# 0007-Optical_Tracker.net
KiCad netlist of a schematic drawn in Altium Designer
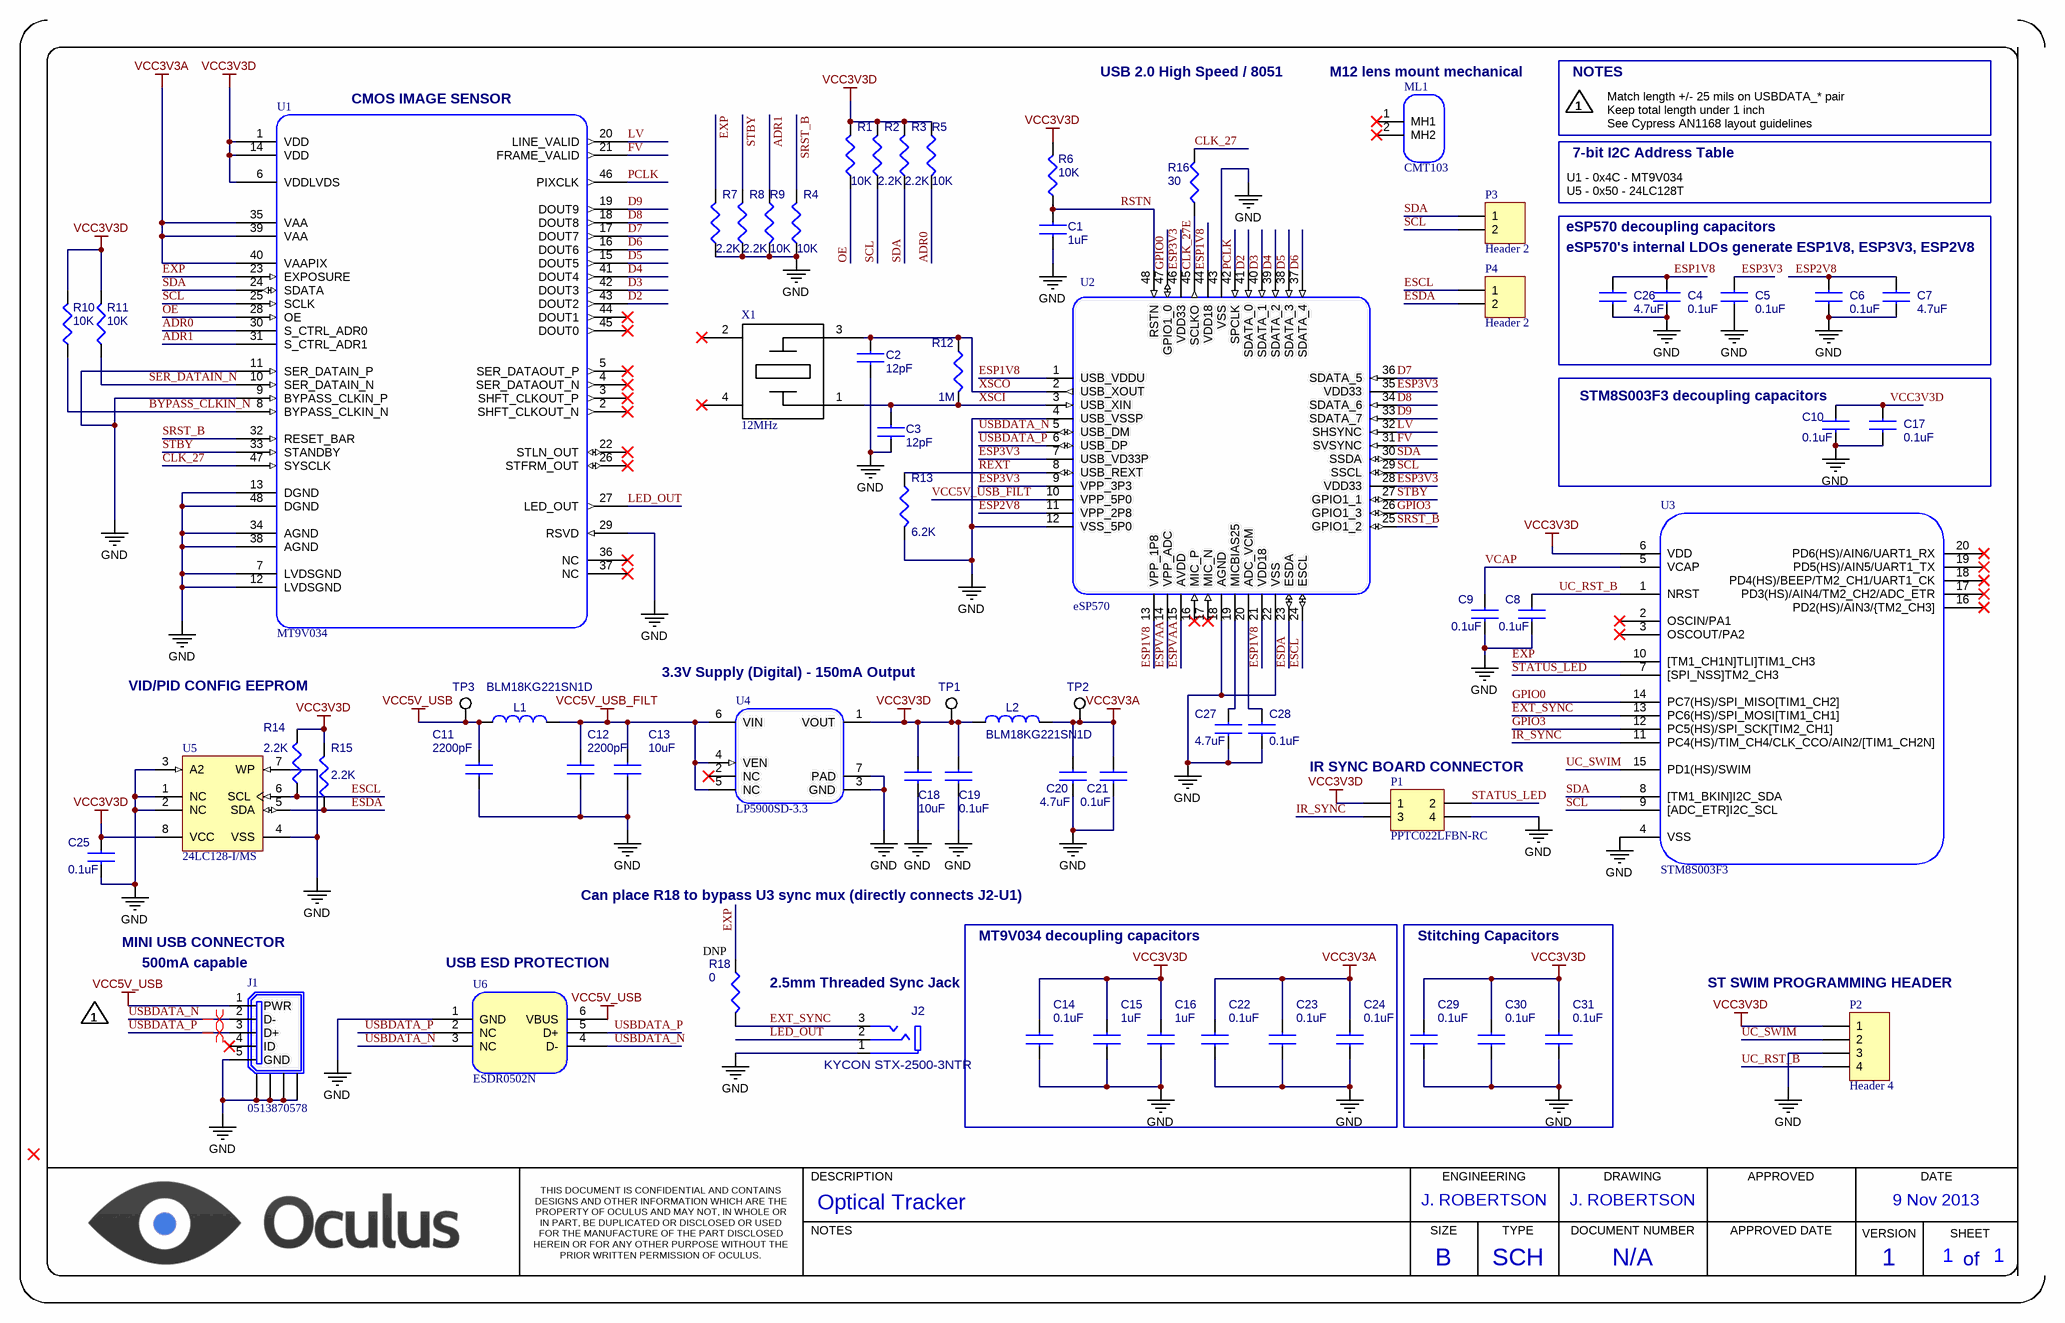
[diagram p0: 0007-Optical_Tracker.SchDoc]

(export (version "E")
  (design (tool "Eeschema 10.0.6"))
  (components
    (comp (ref "C1")
      (value "1uF")
      (footprint "CAP_CERAMIC_0402")
      (description "CAP CER 1UF 6.3V 20% X5R 0402")
      (libsource (lib "SchematicComponents") (part "CAP, CERAMIC"))
    )
    (comp (ref "C2")
      (value "12pF")
      (footprint "CAP_CERAMIC_0402")
      (description "CAP CER 12PF 50V 5% NP0 0402")
      (libsource (lib "SchematicComponents") (part "CAP, CERAMIC"))
    )
    (comp (ref "C3")
      (value "12pF")
      (footprint "CAP_CERAMIC_0402")
      (description "CAP CER 12PF 50V 5% NP0 0402")
      (libsource (lib "SchematicComponents") (part "CAP, CERAMIC"))
    )
    (comp (ref "C4")
      (value "0.1uF")
      (footprint "CAP_CERAMIC_0402")
      (description "CAP CER 0.1UF 6.3V 20% X5R 0402")
      (libsource (lib "SchematicComponents") (part "CAP, CERAMIC"))
    )
    (comp (ref "C5")
      (value "0.1uF")
      (footprint "CAP_CERAMIC_0402")
      (description "CAP CER 0.1UF 6.3V 20% X5R 0402")
      (libsource (lib "SchematicComponents") (part "CAP, CERAMIC"))
    )
    (comp (ref "C6")
      (value "0.1uF")
      (footprint "CAP_CERAMIC_0402")
      (description "CAP CER 0.1UF 6.3V 20% X5R 0402")
      (libsource (lib "SchematicComponents") (part "CAP, CERAMIC"))
    )
    (comp (ref "C7")
      (value "4.7uF")
      (footprint "CAP_CERAMIC_0402")
      (description "CAP CER 4.7UF 6.3V 20% X5R 0402")
      (libsource (lib "SchematicComponents") (part "CAP, CERAMIC"))
    )
    (comp (ref "C8")
      (value "0.1uF")
      (footprint "CAP_CERAMIC_0402")
      (description "CAP CER 0.1UF 6.3V 20% X5R 0402")
      (libsource (lib "SchematicComponents") (part "CAP, CERAMIC"))
    )
    (comp (ref "C9")
      (value "0.1uF")
      (footprint "CAP_CERAMIC_0402")
      (description "CAP CER 0.1UF 6.3V 20% X5R 0402")
      (libsource (lib "SchematicComponents") (part "CAP, CERAMIC"))
    )
    (comp (ref "C10")
      (value "0.1uF")
      (footprint "CAP_CERAMIC_0402")
      (description "CAP CER 0.1UF 6.3V 20% X5R 0402")
      (libsource (lib "SchematicComponents") (part "CAP, CERAMIC"))
    )
    (comp (ref "C11")
      (value "2200pF")
      (footprint "CAP_CERAMIC_0402")
      (description "CAP CER 2200PF 50V 10% X7R 0402")
      (libsource (lib "SchematicComponents") (part "CAP, CERAMIC"))
    )
    (comp (ref "C12")
      (value "2200pF")
      (footprint "CAP_CERAMIC_0402")
      (description "CAP CER 2200PF 50V 10% X7R 0402")
      (libsource (lib "SchematicComponents") (part "CAP, CERAMIC"))
    )
    (comp (ref "C13")
      (value "10uF")
      (footprint "CAP_CERAMIC_0603")
      (description "CAP CER 10UF 6.3V 20% X5R 0603")
      (libsource (lib "SchematicComponents") (part "CAP, CERAMIC"))
    )
    (comp (ref "C14")
      (value "0.1uF")
      (footprint "CAP_CERAMIC_0402")
      (description "CAP CER 0.1UF 6.3V 20% X5R 0402")
      (libsource (lib "SchematicComponents") (part "CAP, CERAMIC"))
    )
    (comp (ref "C15")
      (value "1uF")
      (footprint "CAP_CERAMIC_0402")
      (description "CAP CER 1UF 6.3V 20% X5R 0402")
      (libsource (lib "SchematicComponents") (part "CAP, CERAMIC"))
    )
    (comp (ref "C16")
      (value "1uF")
      (footprint "CAP_CERAMIC_0402")
      (description "CAP CER 1UF 6.3V 20% X5R 0402")
      (libsource (lib "SchematicComponents") (part "CAP, CERAMIC"))
    )
    (comp (ref "C17")
      (value "0.1uF")
      (footprint "CAP_CERAMIC_0402")
      (description "CAP CER 0.1UF 6.3V 20% X5R 0402")
      (libsource (lib "SchematicComponents") (part "CAP, CERAMIC"))
    )
    (comp (ref "C18")
      (value "10uF")
      (footprint "CAP_CERAMIC_0603")
      (description "CAP CER 10UF 6.3V 20% X5R 0603")
      (libsource (lib "SchematicComponents") (part "CAP, CERAMIC"))
    )
    (comp (ref "C19")
      (value "0.1uF")
      (footprint "CAP_CERAMIC_0402")
      (description "CAP CER 0.1UF 6.3V 20% X5R 0402")
      (libsource (lib "SchematicComponents") (part "CAP, CERAMIC"))
    )
    (comp (ref "C20")
      (value "4.7uF")
      (footprint "CAP_CERAMIC_0402")
      (description "CAP CER 4.7UF 6.3V 20% X5R 0402")
      (libsource (lib "SchematicComponents") (part "CAP, CERAMIC"))
    )
    (comp (ref "C21")
      (value "0.1uF")
      (footprint "CAP_CERAMIC_0402")
      (description "CAP CER 0.1UF 6.3V 20% X5R 0402")
      (libsource (lib "SchematicComponents") (part "CAP, CERAMIC"))
    )
    (comp (ref "C22")
      (value "0.1uF")
      (footprint "CAP_CERAMIC_0402")
      (description "CAP CER 0.1UF 6.3V 20% X5R 0402")
      (libsource (lib "SchematicComponents") (part "CAP, CERAMIC"))
    )
    (comp (ref "C23")
      (value "0.1uF")
      (footprint "CAP_CERAMIC_0402")
      (description "CAP CER 0.1UF 6.3V 20% X5R 0402")
      (libsource (lib "SchematicComponents") (part "CAP, CERAMIC"))
    )
    (comp (ref "C24")
      (value "0.1uF")
      (footprint "CAP_CERAMIC_0402")
      (description "CAP CER 0.1UF 6.3V 20% X5R 0402")
      (libsource (lib "SchematicComponents") (part "CAP, CERAMIC"))
    )
    (comp (ref "C25")
      (value "0.1uF")
      (footprint "CAP_CERAMIC_0402")
      (description "CAP CER 0.1UF 6.3V 20% X5R 0402")
      (libsource (lib "SchematicComponents") (part "CAP, CERAMIC"))
    )
    (comp (ref "C26")
      (value "4.7uF")
      (footprint "CAP_CERAMIC_0402")
      (description "CAP CER 4.7UF 6.3V 20% X5R 0402")
      (libsource (lib "SchematicComponents") (part "CAP, CERAMIC"))
    )
    (comp (ref "C27")
      (value "4.7uF")
      (footprint "CAP_CERAMIC_0402")
      (description "CAP CER 4.7UF 6.3V 20% X5R 0402")
      (libsource (lib "SchematicComponents") (part "CAP, CERAMIC"))
    )
    (comp (ref "C28")
      (value "0.1uF")
      (footprint "CAP_CERAMIC_0402")
      (description "CAP CER 0.1UF 6.3V 20% X5R 0402")
      (libsource (lib "SchematicComponents") (part "CAP, CERAMIC"))
    )
    (comp (ref "C29")
      (value "0.1uF")
      (footprint "CAP_CERAMIC_0402")
      (description "CAP CER 0.1UF 6.3V 20% X5R 0402")
      (libsource (lib "SchematicComponents") (part "CAP, CERAMIC"))
    )
    (comp (ref "C30")
      (value "0.1uF")
      (footprint "CAP_CERAMIC_0402")
      (description "CAP CER 0.1UF 6.3V 20% X5R 0402")
      (libsource (lib "SchematicComponents") (part "CAP, CERAMIC"))
    )
    (comp (ref "C31")
      (value "0.1uF")
      (footprint "CAP_CERAMIC_0402")
      (description "CAP CER 0.1UF 6.3V 20% X5R 0402")
      (libsource (lib "SchematicComponents") (part "CAP, CERAMIC"))
    )
    (comp (ref "J1")
      (value "0513870578")
      (footprint "0513870578")
      (description "CONN RECEPT MINIUSB R/A 5POS SMD")
      (libsource (lib "SchematicComponents") (part "0513870578"))
    )
    (comp (ref "J2")
      (value "KYCON STX-2500-3NTR")
      (footprint "KYCON_STX2500")
      (description "Phone Connectors SJ 2.5MM SMT 3POS")
      (libsource (lib "*") (part "AUDIO_JACK_3P"))
    )
    (comp (ref "L1")
      (value "BLM18KG221SN1D")
      (footprint "INDUCTOR_0603")
      (description "FERRITE CHIP 220 OHM 2200MA 0603")
      (fields (field (name "MANUFACTURER") "Murata"))
      (libsource (lib "SchematicComponents") (part "INDUCTOR"))
    )
    (comp (ref "L2")
      (value "BLM18KG221SN1D")
      (footprint "INDUCTOR_0603")
      (description "FERRITE CHIP 220 OHM 2200MA 0603")
      (fields (field (name "MANUFACTURER") "Murata"))
      (libsource (lib "SchematicComponents") (part "INDUCTOR"))
    )
    (comp (ref "ML1")
      (value "CMT103")
      (footprint "CMT103")
      (description "Lens holder, M12x0.5, 16.2, centered")
      (libsource (lib "SchematicComponents") (part "CMT103"))
    )
    (comp (ref "P1")
      (value "PPTC022LFBN-RC")
      (footprint "HDR2X2")
      (description "Header, 2-Pin, Dual row")
      (libsource (lib "Miscellaneous Connectors") (part "Header 2X2"))
    )
    (comp (ref "P2")
      (value "Header 4")
      (footprint "HDR1X4")
      (description "Header, 4-Pin")
      (libsource (lib "Miscellaneous Connectors") (part "Header 4"))
    )
    (comp (ref "P3")
      (value "Header 2")
      (footprint "HDR1X2")
      (description "Header, 2-Pin")
      (fields (field (name "PUBLISHER") "Altium Limited"))
      (libsource (lib "Miscellaneous Connectors") (part "Header 2"))
    )
    (comp (ref "P4")
      (value "Header 2")
      (footprint "HDR1X2")
      (description "Header, 2-Pin")
      (fields (field (name "PUBLISHER") "Altium Limited"))
      (libsource (lib "Miscellaneous Connectors") (part "Header 2"))
    )
    (comp (ref "R1")
      (value "10K")
      (footprint "RESISTOR_0402")
      (description "RES 10K OHM 1/10W 1% 0402 SMD")
      (libsource (lib "SchematicComponents") (part "RESISTOR"))
    )
    (comp (ref "R2")
      (value "2.2K")
      (footprint "RESISTOR_0402")
      (description "RES 2.2K OHM 1/10W 1% 0402 SMD")
      (libsource (lib "SchematicComponents") (part "RESISTOR"))
    )
    (comp (ref "R3")
      (value "2.2K")
      (footprint "RESISTOR_0402")
      (description "RES 2.2K OHM 1/10W 1% 0402 SMD")
      (libsource (lib "SchematicComponents") (part "RESISTOR"))
    )
    (comp (ref "R4")
      (value "10K")
      (footprint "RESISTOR_0402")
      (description "RES 10K OHM 1/10W 1% 0402 SMD")
      (libsource (lib "SchematicComponents") (part "RESISTOR"))
    )
    (comp (ref "R5")
      (value "10K")
      (footprint "RESISTOR_0402")
      (description "RES 10K OHM 1/10W 1% 0402 SMD")
      (libsource (lib "SchematicComponents") (part "RESISTOR"))
    )
    (comp (ref "R6")
      (value "10K")
      (footprint "RESISTOR_0402")
      (description "RES 10K OHM 1/10W 1% 0402 SMD")
      (libsource (lib "SchematicComponents") (part "RESISTOR"))
    )
    (comp (ref "R7")
      (value "2.2K")
      (footprint "RESISTOR_0402")
      (description "RES 2.2K OHM 1/10W 1% 0402 SMD")
      (libsource (lib "SchematicComponents") (part "RESISTOR"))
    )
    (comp (ref "R8")
      (value "2.2K")
      (footprint "RESISTOR_0402")
      (description "RES 2.2K OHM 1/10W 1% 0402 SMD")
      (libsource (lib "SchematicComponents") (part "RESISTOR"))
    )
    (comp (ref "R9")
      (value "10K")
      (footprint "RESISTOR_0402")
      (description "RES 10K OHM 1/10W 1% 0402 SMD")
      (libsource (lib "SchematicComponents") (part "RESISTOR"))
    )
    (comp (ref "R10")
      (value "10K")
      (footprint "RESISTOR_0402")
      (description "RES 10K OHM 1/10W 1% 0402 SMD")
      (libsource (lib "SchematicComponents") (part "RESISTOR"))
    )
    (comp (ref "R11")
      (value "10K")
      (footprint "RESISTOR_0402")
      (description "RES 10K OHM 1/10W 1% 0402 SMD")
      (libsource (lib "SchematicComponents") (part "RESISTOR"))
    )
    (comp (ref "R12")
      (value "1M")
      (footprint "RESISTOR_0402")
      (description "RES 1M OHM 1/10W 1% 0402 SMD")
      (libsource (lib "SchematicComponents") (part "RESISTOR"))
    )
    (comp (ref "R13")
      (value "6.2K")
      (footprint "RESISTOR_0402")
      (description "RES 6.2K OHM 1/10W 1% 0402 SMD")
      (libsource (lib "SchematicComponents") (part "RESISTOR"))
    )
    (comp (ref "R14")
      (value "2.2K")
      (footprint "RESISTOR_0402")
      (description "RES 2.2K OHM 1/10W 1% 0402 SMD")
      (libsource (lib "SchematicComponents") (part "RESISTOR"))
    )
    (comp (ref "R15")
      (value "2.2K")
      (footprint "RESISTOR_0402")
      (description "RES 2.2K OHM 1/10W 1% 0402 SMD")
      (libsource (lib "SchematicComponents") (part "RESISTOR"))
    )
    (comp (ref "R16")
      (value "30")
      (footprint "RESISTOR_0402")
      (description "RES 30 OHM 1/10W 1% 0402 SMD")
      (libsource (lib "SchematicComponents") (part "RESISTOR"))
    )
    (comp (ref "R18")
      (value "0")
      (footprint "RESISTOR_0402")
      (description "RES 0 OHM 1/10W 1% 0402 SMD")
      (libsource (lib "SchematicComponents") (part "RESISTOR"))
    )
    (comp (ref "TP1")
      (value "TEST POINT")
      (footprint "TEST_POINT_PAD")
      (libsource (lib "SchematicComponents") (part "TEST_POINT"))
    )
    (comp (ref "TP2")
      (value "TEST POINT")
      (footprint "TEST_POINT_PAD")
      (libsource (lib "SchematicComponents") (part "TEST_POINT"))
    )
    (comp (ref "TP3")
      (value "TEST POINT")
      (footprint "TEST_POINT_PAD")
      (libsource (lib "SchematicComponents") (part "TEST_POINT"))
    )
    (comp (ref "U1")
      (value "MT9V034")
      (footprint "CLCC-48")
      (description "1/3\" WVGA 60FPS CMOS Digital Image Sensor Global Shutter")
      (fields (field (name "PART NUMBER") "MT9V034C12STC"))
      (libsource (lib "SchematicComponents") (part "MT9V034_DS_D"))
    )
    (comp (ref "U2")
      (value "eSP570")
      (footprint "LQFP-48_M")
      (description "USB 2.0 Camera Bridge Controller")
      (libsource (lib "SchematicComponents") (part "eSP570"))
    )
    (comp (ref "U3")
      (value "STM8S003F3")
      (footprint "20-UFQFN")
      (description "MCU 8BIT 8KB 16MHZ")
      (libsource (lib "0007-Optical_Tracker") (part "STM8S003F3"))
    )
    (comp (ref "U4")
      (value "LP5900SD-3.3")
      (footprint "LLP-6")
      (description "IC, LINEAR REGULATOR, 3.3V, 150MA, ULTRA LOW NOISE")
      (fields
        (field (name "MANUFACTURER") "NATIONAL SEMICONDUCTOR")
        (field (name "PART NUMBER") "LP5900SD-3.3/NOPB")
      )
      (libsource (lib "SchematicComponents") (part "LP5900SD-3.3"))
    )
    (comp (ref "U5")
      (value "24LC128-I/MS")
      (footprint "MSOP-MS8_N")
      (description "128Kbit, 400kHz, 2.5V, I2C Serial EEPROM, 8-Pin MSOP, Industrial Temperature")
      (fields (field (name "PUBLISHER") "Altium Limited"))
      (libsource (lib "Microchip Memory I2C Serial EEPROM") (part "24LC128-I/MS"))
    )
    (comp (ref "U6")
      (value "ESDR0502N")
      (footprint "UDFN-6")
      (description "TVS ARRAY LOW CAP 6UDFN")
      (libsource (lib "SchematicComponents") (part "ESDR0502N"))
    )
    (comp (ref "X1")
      (value "12MHz")
      (footprint "4-SMD")
      (description "CRYSTAL 12MHZ 20PF SMD")
      (libsource (lib "SchematicComponents") (part "405C35E24M00000"))
    )
  )
  (nets
    (net (code "1") (name "/ADR0") (class "Default")
      (node (ref "R5") (pin "2") (pinfunction "2_2") (pintype "passive"))
      (node (ref "U1") (pin "30") (pinfunction "S_CTRL_ADR0_30") (pintype "open_collector"))
    )
    (net (code "2") (name "/ADR1") (class "Default")
      (node (ref "R9") (pin "1") (pinfunction "1_1") (pintype "passive"))
      (node (ref "U1") (pin "31") (pinfunction "S_CTRL_ADR1_31") (pintype "open_collector"))
    )
    (net (code "3") (name "/BYPASS_CLKIN_N") (class "Default")
      (node (ref "R10") (pin "1") (pinfunction "1_1") (pintype "passive"))
      (node (ref "U1") (pin "8") (pinfunction "BYPASS_CLKIN_N_8") (pintype "input"))
    )
    (net (code "4") (name "/CLK_27") (class "Default")
      (node (ref "R16") (pin "2") (pinfunction "2_2") (pintype "passive"))
      (node (ref "U1") (pin "47") (pinfunction "SYSCLK_47") (pintype "input"))
    )
    (net (code "5") (name "/CLK_27E") (class "Default")
      (node (ref "R16") (pin "1") (pinfunction "1_1") (pintype "passive"))
      (node (ref "U2") (pin "45") (pinfunction "SCLKO_45") (pintype "output"))
    )
    (net (code "6") (name "/D2") (class "Default")
      (node (ref "U1") (pin "43") (pinfunction "DOUT2_43") (pintype "output"))
      (node (ref "U2") (pin "41") (pinfunction "SDATA_0_41") (pintype "input"))
    )
    (net (code "7") (name "/D3") (class "Default")
      (node (ref "U1") (pin "42") (pinfunction "DOUT3_42") (pintype "output"))
      (node (ref "U2") (pin "40") (pinfunction "SDATA_1_40") (pintype "input"))
    )
    (net (code "8") (name "/D4") (class "Default")
      (node (ref "U1") (pin "41") (pinfunction "DOUT4_41") (pintype "output"))
      (node (ref "U2") (pin "39") (pinfunction "SDATA_2_39") (pintype "input"))
    )
    (net (code "9") (name "/D5") (class "Default")
      (node (ref "U1") (pin "15") (pinfunction "DOUT5_15") (pintype "output"))
      (node (ref "U2") (pin "38") (pinfunction "SDATA_3_38") (pintype "input"))
    )
    (net (code "10") (name "/D6") (class "Default")
      (node (ref "U1") (pin "16") (pinfunction "DOUT6_16") (pintype "output"))
      (node (ref "U2") (pin "37") (pinfunction "SDATA_4_37") (pintype "input"))
    )
    (net (code "11") (name "/D7") (class "Default")
      (node (ref "U1") (pin "17") (pinfunction "DOUT7_17") (pintype "output"))
      (node (ref "U2") (pin "36") (pinfunction "SDATA_5_36") (pintype "input"))
    )
    (net (code "12") (name "/D8") (class "Default")
      (node (ref "U1") (pin "18") (pinfunction "DOUT8_18") (pintype "output"))
      (node (ref "U2") (pin "34") (pinfunction "SDATA_6_34") (pintype "input"))
    )
    (net (code "13") (name "/D9") (class "Default")
      (node (ref "U1") (pin "19") (pinfunction "DOUT9_19") (pintype "output"))
      (node (ref "U2") (pin "33") (pinfunction "SDATA_7_33") (pintype "input"))
    )
    (net (code "14") (name "/ESCL") (class "Default")
      (node (ref "P4") (pin "1") (pinfunction "1_1") (pintype "passive"))
      (node (ref "R14") (pin "1") (pinfunction "1_1") (pintype "passive"))
      (node (ref "U2") (pin "24") (pinfunction "ESCL_24") (pintype "bidirectional"))
      (node (ref "U5") (pin "6") (pinfunction "SCL_6") (pintype "input"))
    )
    (net (code "15") (name "/ESDA") (class "Default")
      (node (ref "P4") (pin "2") (pinfunction "2_2") (pintype "passive"))
      (node (ref "R15") (pin "1") (pinfunction "1_1") (pintype "passive"))
      (node (ref "U2") (pin "23") (pinfunction "ESDA_23") (pintype "bidirectional"))
      (node (ref "U5") (pin "5") (pinfunction "SDA_5") (pintype "bidirectional"))
    )
    (net (code "16") (name "/ESP1V8") (class "Default")
      (node (ref "C26") (pin "1") (pinfunction "1_1") (pintype "passive"))
      (node (ref "C4") (pin "1") (pinfunction "1_1") (pintype "passive"))
      (node (ref "U2") (pin "1") (pinfunction "USB_VDDU_1") (pintype "power_in"))
      (node (ref "U2") (pin "13") (pinfunction "VPP_1P8_13") (pintype "power_in"))
      (node (ref "U2") (pin "21") (pinfunction "VDD18_21") (pintype "power_in"))
      (node (ref "U2") (pin "44") (pinfunction "VDD18_44") (pintype "power_in"))
    )
    (net (code "17") (name "/ESP2V8") (class "Default")
      (node (ref "C6") (pin "1") (pinfunction "1_1") (pintype "passive"))
      (node (ref "C7") (pin "1") (pinfunction "1_1") (pintype "passive"))
      (node (ref "U2") (pin "11") (pinfunction "VPP_2P8_11") (pintype "power_in"))
    )
    (net (code "18") (name "/ESP3V3") (class "Default")
      (node (ref "C5") (pin "1") (pinfunction "1_1") (pintype "passive"))
      (node (ref "U2") (pin "28") (pinfunction "VDD33_28") (pintype "power_in"))
      (node (ref "U2") (pin "35") (pinfunction "VDD33_35") (pintype "power_in"))
      (node (ref "U2") (pin "46") (pinfunction "VDD33_46") (pintype "power_in"))
      (node (ref "U2") (pin "7") (pinfunction "USB_VD33P_7") (pintype "power_in"))
      (node (ref "U2") (pin "9") (pinfunction "VPP_3P3_9") (pintype "power_in"))
    )
    (net (code "19") (name "/ESPVAA") (class "Default")
      (node (ref "U2") (pin "14") (pinfunction "VPP_ADC_14") (pintype "power_in"))
      (node (ref "U2") (pin "15") (pinfunction "AVDD_15") (pintype "power_in"))
    )
    (net (code "20") (name "/EXP") (class "Default")
      (node (ref "R18") (pin "1") (pinfunction "1_1") (pintype "passive"))
      (node (ref "R7") (pin "2") (pinfunction "2_2") (pintype "passive"))
      (node (ref "U1") (pin "23") (pinfunction "EXPOSURE_23") (pintype "input"))
      (node (ref "U3") (pin "10") (pinfunction "[TM1_CH1N]TLI]TIM1_CH3_10") (pintype "passive"))
    )
    (net (code "21") (name "/EXT_SYNC") (class "Default")
      (node (ref "J2") (pin "3") (pinfunction "3_3") (pintype "passive"))
      (node (ref "R18") (pin "2") (pinfunction "2_2") (pintype "passive"))
      (node (ref "U3") (pin "13") (pinfunction "PC6(HS)/SPI_MOSI[TIM1_CH1]_13") (pintype "passive"))
    )
    (net (code "22") (name "/FV") (class "Default")
      (node (ref "U1") (pin "21") (pinfunction "FRAME_VALID_21") (pintype "output"))
      (node (ref "U2") (pin "31") (pinfunction "SVSYNC_31") (pintype "input"))
    )
    (net (code "23") (name "/GPIO0") (class "Default")
      (node (ref "U2") (pin "47") (pinfunction "GPIO1_0_47") (pintype "bidirectional"))
      (node (ref "U3") (pin "14") (pinfunction "PC7(HS)/SPI_MISO[TIM1_CH2]_14") (pintype "passive"))
    )
    (net (code "24") (name "/GPIO3") (class "Default")
      (node (ref "U2") (pin "26") (pinfunction "GPIO1_3_26") (pintype "bidirectional"))
      (node (ref "U3") (pin "12") (pinfunction "PC5(HS)/SPI_SCK[TIM2_CH1]_12") (pintype "passive"))
    )
    (net (code "25") (name "/IR_SYNC") (class "Default")
      (node (ref "P1") (pin "3") (pinfunction "3_3") (pintype "passive"))
      (node (ref "U3") (pin "11") (pinfunction "PC4(HS)/TIM_CH4/CLK_CCO/AIN2/[TIM1_CH2N]_11") (pintype "passive"))
    )
    (net (code "26") (name "/LED_OUT") (class "Default")
      (node (ref "J2") (pin "2") (pinfunction "2_2") (pintype "passive"))
      (node (ref "U1") (pin "27") (pinfunction "LED_OUT_27") (pintype "output"))
    )
    (net (code "27") (name "/LV") (class "Default")
      (node (ref "U1") (pin "20") (pinfunction "LINE_VALID_20") (pintype "output"))
      (node (ref "U2") (pin "32") (pinfunction "SHSYNC_32") (pintype "input"))
    )
    (net (code "28") (name "/OE") (class "Default")
      (node (ref "R1") (pin "1") (pinfunction "1_1") (pintype "passive"))
      (node (ref "U1") (pin "28") (pinfunction "OE_28") (pintype "input"))
    )
    (net (code "29") (name "/PCLK") (class "Default")
      (node (ref "U1") (pin "46") (pinfunction "PIXCLK_46") (pintype "output"))
      (node (ref "U2") (pin "42") (pinfunction "SPCLK_42") (pintype "input"))
    )
    (net (code "30") (name "/REXT") (class "Default")
      (node (ref "R13") (pin "1") (pinfunction "1_1") (pintype "passive"))
      (node (ref "U2") (pin "8") (pinfunction "USB_REXT_8") (pintype "bidirectional"))
    )
    (net (code "31") (name "/RSTN") (class "Default")
      (node (ref "C1") (pin "2") (pinfunction "2_2") (pintype "passive"))
      (node (ref "R6") (pin "1") (pinfunction "1_1") (pintype "passive"))
      (node (ref "U2") (pin "48") (pinfunction "RSTN_48") (pintype "input"))
    )
    (net (code "32") (name "/SCL") (class "Default")
      (node (ref "P3") (pin "2") (pinfunction "2_2") (pintype "passive"))
      (node (ref "R2") (pin "1") (pinfunction "1_1") (pintype "passive"))
      (node (ref "U1") (pin "25") (pinfunction "SCLK_25") (pintype "input"))
      (node (ref "U2") (pin "29") (pinfunction "SSCL_29") (pintype "bidirectional"))
      (node (ref "U3") (pin "9") (pinfunction "[ADC_ETR]I2C_SCL_9") (pintype "passive"))
    )
    (net (code "33") (name "/SDA") (class "Default")
      (node (ref "P3") (pin "1") (pinfunction "1_1") (pintype "passive"))
      (node (ref "R3") (pin "1") (pinfunction "1_1") (pintype "passive"))
      (node (ref "U1") (pin "24") (pinfunction "SDATA_24") (pintype "bidirectional"))
      (node (ref "U2") (pin "30") (pinfunction "SSDA_30") (pintype "bidirectional"))
      (node (ref "U3") (pin "8") (pinfunction "[TM1_BKIN]I2C_SDA_8") (pintype "passive"))
    )
    (net (code "34") (name "/SER_DATAIN_N") (class "Default")
      (node (ref "R11") (pin "1") (pinfunction "1_1") (pintype "passive"))
      (node (ref "U1") (pin "10") (pinfunction "SER_DATAIN_N_10") (pintype "input"))
    )
    (net (code "35") (name "/SRST_B") (class "Default")
      (node (ref "R4") (pin "2") (pinfunction "2_2") (pintype "passive"))
      (node (ref "U1") (pin "32") (pinfunction "RESET_BAR_32") (pintype "input"))
      (node (ref "U2") (pin "25") (pinfunction "GPIO1_2_25") (pintype "bidirectional"))
    )
    (net (code "36") (name "/STATUS_LED") (class "Default")
      (node (ref "P1") (pin "2") (pinfunction "2_2") (pintype "passive"))
      (node (ref "U3") (pin "7") (pinfunction "[SPI_NSS]TM2_CH3_7") (pintype "passive"))
    )
    (net (code "37") (name "/STBY") (class "Default")
      (node (ref "R8") (pin "2") (pinfunction "2_2") (pintype "passive"))
      (node (ref "U1") (pin "33") (pinfunction "STANDBY_33") (pintype "input"))
      (node (ref "U2") (pin "27") (pinfunction "GPIO1_1_27") (pintype "bidirectional"))
    )
    (net (code "38") (name "/UC_RST_B") (class "Default")
      (node (ref "C8") (pin "1") (pinfunction "1_1") (pintype "passive"))
      (node (ref "P2") (pin "4") (pinfunction "4_4") (pintype "passive"))
      (node (ref "U3") (pin "1") (pinfunction "NRST_1") (pintype "passive"))
    )
    (net (code "39") (name "/UC_SWIM") (class "Default")
      (node (ref "P2") (pin "2") (pinfunction "2_2") (pintype "passive"))
      (node (ref "U3") (pin "15") (pinfunction "PD1(HS)/SWIM_15") (pintype "passive"))
    )
    (net (code "40") (name "/USBDATA_N") (class "Default")
      (node (ref "J1") (pin "2") (pinfunction "D-_2") (pintype "tri_state"))
      (node (ref "U2") (pin "5") (pinfunction "USB_DM_5") (pintype "bidirectional"))
      (node (ref "U6") (pin "3") (pinfunction "NC_3") (pintype "passive"))
      (node (ref "U6") (pin "4") (pinfunction "D-_4") (pintype "power_in"))
    )
    (net (code "41") (name "/USBDATA_P") (class "Default")
      (node (ref "J1") (pin "3") (pinfunction "D+_3") (pintype "tri_state"))
      (node (ref "U2") (pin "6") (pinfunction "USB_DP_6") (pintype "bidirectional"))
      (node (ref "U6") (pin "2") (pinfunction "NC_2") (pintype "passive"))
      (node (ref "U6") (pin "5") (pinfunction "D+_5") (pintype "power_in"))
    )
    (net (code "42") (name "/VCAP") (class "Default")
      (node (ref "C9") (pin "1") (pinfunction "1_1") (pintype "passive"))
      (node (ref "U3") (pin "5") (pinfunction "VCAP_5") (pintype "power_in"))
    )
    (net (code "43") (name "/XSCI") (class "Default")
      (node (ref "C3") (pin "2") (pinfunction "2_2") (pintype "passive"))
      (node (ref "R12") (pin "2") (pinfunction "2_2") (pintype "passive"))
      (node (ref "U2") (pin "3") (pinfunction "USB_XIN_3") (pintype "input"))
      (node (ref "X1") (pin "1") (pinfunction "1_1") (pintype "passive"))
    )
    (net (code "44") (name "/XSCO") (class "Default")
      (node (ref "C2") (pin "2") (pinfunction "2_2") (pintype "passive"))
      (node (ref "R12") (pin "1") (pinfunction "1_1") (pintype "passive"))
      (node (ref "U2") (pin "2") (pinfunction "USB_XOUT_2") (pintype "output"))
      (node (ref "X1") (pin "3") (pinfunction "3_3") (pintype "passive"))
    )
    (net (code "45") (name "GND") (class "Default")
      (node (ref "C1") (pin "1") (pinfunction "1_1") (pintype "passive"))
      (node (ref "C10") (pin "2") (pinfunction "2_2") (pintype "passive"))
      (node (ref "C11") (pin "2") (pinfunction "2_2") (pintype "passive"))
      (node (ref "C12") (pin "2") (pinfunction "2_2") (pintype "passive"))
      (node (ref "C13") (pin "2") (pinfunction "2_2") (pintype "passive"))
      (node (ref "C14") (pin "2") (pinfunction "2_2") (pintype "passive"))
      (node (ref "C15") (pin "2") (pinfunction "2_2") (pintype "passive"))
      (node (ref "C16") (pin "2") (pinfunction "2_2") (pintype "passive"))
      (node (ref "C17") (pin "2") (pinfunction "2_2") (pintype "passive"))
      (node (ref "C18") (pin "2") (pinfunction "2_2") (pintype "passive"))
      (node (ref "C19") (pin "2") (pinfunction "2_2") (pintype "passive"))
      (node (ref "C2") (pin "1") (pinfunction "1_1") (pintype "passive"))
      (node (ref "C20") (pin "2") (pinfunction "2_2") (pintype "passive"))
      (node (ref "C21") (pin "2") (pinfunction "2_2") (pintype "passive"))
      (node (ref "C22") (pin "2") (pinfunction "2_2") (pintype "passive"))
      (node (ref "C23") (pin "2") (pinfunction "2_2") (pintype "passive"))
      (node (ref "C24") (pin "2") (pinfunction "2_2") (pintype "passive"))
      (node (ref "C25") (pin "2") (pinfunction "2_2") (pintype "passive"))
      (node (ref "C26") (pin "2") (pinfunction "2_2") (pintype "passive"))
      (node (ref "C27") (pin "2") (pinfunction "2_2") (pintype "passive"))
      (node (ref "C28") (pin "2") (pinfunction "2_2") (pintype "passive"))
      (node (ref "C29") (pin "2") (pinfunction "2_2") (pintype "passive"))
      (node (ref "C3") (pin "1") (pinfunction "1_1") (pintype "passive"))
      (node (ref "C30") (pin "2") (pinfunction "2_2") (pintype "passive"))
      (node (ref "C31") (pin "2") (pinfunction "2_2") (pintype "passive"))
      (node (ref "C4") (pin "2") (pinfunction "2_2") (pintype "passive"))
      (node (ref "C5") (pin "2") (pinfunction "2_2") (pintype "passive"))
      (node (ref "C6") (pin "2") (pinfunction "2_2") (pintype "passive"))
      (node (ref "C7") (pin "2") (pinfunction "2_2") (pintype "passive"))
      (node (ref "C8") (pin "2") (pinfunction "2_2") (pintype "passive"))
      (node (ref "C9") (pin "2") (pinfunction "2_2") (pintype "passive"))
      (node (ref "J1") (pin "5") (pinfunction "GND_5") (pintype "power_in"))
      (node (ref "J1") (pin "6") (pinfunction "SHIELD_6") (pintype "passive"))
      (node (ref "J1") (pin "7") (pinfunction "SHIELD_7") (pintype "passive"))
      (node (ref "J1") (pin "8") (pinfunction "SHIELD_8") (pintype "passive"))
      (node (ref "J1") (pin "9") (pinfunction "SHIELD_9") (pintype "passive"))
      (node (ref "J2") (pin "1") (pinfunction "1_1") (pintype "passive"))
      (node (ref "P1") (pin "4") (pinfunction "4_4") (pintype "passive"))
      (node (ref "P2") (pin "3") (pinfunction "3_3") (pintype "passive"))
      (node (ref "R13") (pin "2") (pinfunction "2_2") (pintype "passive"))
      (node (ref "R4") (pin "1") (pinfunction "1_1") (pintype "passive"))
      (node (ref "R7") (pin "1") (pinfunction "1_1") (pintype "passive"))
      (node (ref "R8") (pin "1") (pinfunction "1_1") (pintype "passive"))
      (node (ref "R9") (pin "2") (pinfunction "2_2") (pintype "passive"))
      (node (ref "U1") (pin "11") (pinfunction "SER_DATAIN_P_11") (pintype "input"))
      (node (ref "U1") (pin "12") (pinfunction "LVDSGND_12") (pintype "power_in"))
      (node (ref "U1") (pin "13") (pinfunction "DGND_13") (pintype "power_in"))
      (node (ref "U1") (pin "29") (pinfunction "RSVD_29") (pintype "input"))
      (node (ref "U1") (pin "34") (pinfunction "AGND_34") (pintype "power_in"))
      (node (ref "U1") (pin "38") (pinfunction "AGND_38") (pintype "power_in"))
      (node (ref "U1") (pin "48") (pinfunction "DGND_48") (pintype "power_in"))
      (node (ref "U1") (pin "7") (pinfunction "LVDSGND_7") (pintype "power_in"))
      (node (ref "U1") (pin "9") (pinfunction "BYPASS_CLKIN_P_9") (pintype "input"))
      (node (ref "U2") (pin "12") (pinfunction "VSS_5P0_12") (pintype "power_in"))
      (node (ref "U2") (pin "18") (pinfunction "AGND_18") (pintype "power_in"))
      (node (ref "U2") (pin "22") (pinfunction "VSS_22") (pintype "power_in"))
      (node (ref "U2") (pin "4") (pinfunction "USB_VSSP_4") (pintype "power_in"))
      (node (ref "U2") (pin "43") (pinfunction "VSS_43") (pintype "power_in"))
      (node (ref "U3") (pin "4") (pinfunction "VSS_4") (pintype "power_in"))
      (node (ref "U4") (pin "3") (pinfunction "GND_3") (pintype "power_in"))
      (node (ref "U4") (pin "7") (pinfunction "PAD_7") (pintype "power_in"))
      (node (ref "U5") (pin "1") (pinfunction "NC_1") (pintype "passive"))
      (node (ref "U5") (pin "2") (pinfunction "NC_2") (pintype "passive"))
      (node (ref "U5") (pin "3") (pinfunction "A2_3") (pintype "input"))
      (node (ref "U5") (pin "4") (pinfunction "VSS_4") (pintype "power_in"))
      (node (ref "U5") (pin "7") (pinfunction "WP_7") (pintype "input"))
      (node (ref "U6") (pin "1") (pinfunction "GND_1") (pintype "power_in"))
    )
    (net (code "46") (name "Net-(U2-ADC_VCM)") (class "Default")
      (node (ref "C28") (pin "1") (pinfunction "1_1") (pintype "passive"))
      (node (ref "U2") (pin "20") (pinfunction "ADC_VCM_20") (pintype "power_in"))
    )
    (net (code "47") (name "Net-(U2-MICBIAS25)") (class "Default")
      (node (ref "C27") (pin "1") (pinfunction "1_1") (pintype "passive"))
      (node (ref "U2") (pin "19") (pinfunction "MICBIAS25_19") (pintype "power_in"))
    )
    (net (code "48") (name "VCC3V3A") (class "Default")
      (node (ref "C20") (pin "1") (pinfunction "1_1") (pintype "passive"))
      (node (ref "C21") (pin "1") (pinfunction "1_1") (pintype "passive"))
      (node (ref "C22") (pin "1") (pinfunction "1_1") (pintype "passive"))
      (node (ref "C23") (pin "1") (pinfunction "1_1") (pintype "passive"))
      (node (ref "C24") (pin "1") (pinfunction "1_1") (pintype "passive"))
      (node (ref "L2") (pin "2") (pinfunction "2_2") (pintype "passive"))
      (node (ref "TP2") (pin "1") (pinfunction "1_1") (pintype "passive"))
      (node (ref "U1") (pin "35") (pinfunction "VAA_35") (pintype "power_in"))
      (node (ref "U1") (pin "39") (pinfunction "VAA_39") (pintype "power_in"))
      (node (ref "U1") (pin "40") (pinfunction "VAAPIX_40") (pintype "power_in"))
    )
    (net (code "49") (name "VCC3V3D") (class "Default")
      (node (ref "C10") (pin "1") (pinfunction "1_1") (pintype "passive"))
      (node (ref "C14") (pin "1") (pinfunction "1_1") (pintype "passive"))
      (node (ref "C15") (pin "1") (pinfunction "1_1") (pintype "passive"))
      (node (ref "C16") (pin "1") (pinfunction "1_1") (pintype "passive"))
      (node (ref "C17") (pin "1") (pinfunction "1_1") (pintype "passive"))
      (node (ref "C18") (pin "1") (pinfunction "1_1") (pintype "passive"))
      (node (ref "C19") (pin "1") (pinfunction "1_1") (pintype "passive"))
      (node (ref "C25") (pin "1") (pinfunction "1_1") (pintype "passive"))
      (node (ref "C29") (pin "1") (pinfunction "1_1") (pintype "passive"))
      (node (ref "C30") (pin "1") (pinfunction "1_1") (pintype "passive"))
      (node (ref "C31") (pin "1") (pinfunction "1_1") (pintype "passive"))
      (node (ref "L2") (pin "1") (pinfunction "1_1") (pintype "passive"))
      (node (ref "P1") (pin "1") (pinfunction "1_1") (pintype "passive"))
      (node (ref "P2") (pin "1") (pinfunction "1_1") (pintype "passive"))
      (node (ref "R1") (pin "2") (pinfunction "2_2") (pintype "passive"))
      (node (ref "R10") (pin "2") (pinfunction "2_2") (pintype "passive"))
      (node (ref "R11") (pin "2") (pinfunction "2_2") (pintype "passive"))
      (node (ref "R14") (pin "2") (pinfunction "2_2") (pintype "passive"))
      (node (ref "R15") (pin "2") (pinfunction "2_2") (pintype "passive"))
      (node (ref "R2") (pin "2") (pinfunction "2_2") (pintype "passive"))
      (node (ref "R3") (pin "2") (pinfunction "2_2") (pintype "passive"))
      (node (ref "R5") (pin "1") (pinfunction "1_1") (pintype "passive"))
      (node (ref "R6") (pin "2") (pinfunction "2_2") (pintype "passive"))
      (node (ref "TP1") (pin "1") (pinfunction "1_1") (pintype "passive"))
      (node (ref "U1") (pin "1") (pinfunction "VDD_1") (pintype "power_in"))
      (node (ref "U1") (pin "14") (pinfunction "VDD_14") (pintype "power_in"))
      (node (ref "U1") (pin "6") (pinfunction "VDDLVDS_6") (pintype "power_in"))
      (node (ref "U3") (pin "6") (pinfunction "VDD_6") (pintype "power_in"))
      (node (ref "U4") (pin "1") (pinfunction "VOUT_1") (pintype "power_in"))
      (node (ref "U5") (pin "8") (pinfunction "VCC_8") (pintype "power_in"))
    )
    (net (code "50") (name "VCC5V_USB") (class "Default")
      (node (ref "C11") (pin "1") (pinfunction "1_1") (pintype "passive"))
      (node (ref "J1") (pin "1") (pinfunction "PWR_1") (pintype "power_in"))
      (node (ref "L1") (pin "1") (pinfunction "1_1") (pintype "passive"))
      (node (ref "TP3") (pin "1") (pinfunction "1_1") (pintype "passive"))
      (node (ref "U6") (pin "6") (pinfunction "VBUS_6") (pintype "power_in"))
    )
    (net (code "51") (name "VCC5V_USB_FILT") (class "Default")
      (node (ref "C12") (pin "1") (pinfunction "1_1") (pintype "passive"))
      (node (ref "C13") (pin "1") (pinfunction "1_1") (pintype "passive"))
      (node (ref "L1") (pin "2") (pinfunction "2_2") (pintype "passive"))
      (node (ref "U2") (pin "10") (pinfunction "VPP_5P0_10") (pintype "power_in"))
      (node (ref "U4") (pin "4") (pinfunction "VEN_4") (pintype "input"))
      (node (ref "U4") (pin "5") (pinfunction "NC_5") (pintype "passive"))
      (node (ref "U4") (pin "6") (pinfunction "VIN_6") (pintype "power_in"))
    )
    (net (code "52") (name "unconnected-(J1-ID-Pad4)") (class "Default")
      (node (ref "J1") (pin "4") (pinfunction "ID_4") (pintype "passive+no_connect"))
    )
    (net (code "53") (name "unconnected-(ML1-MH1-Pad1)") (class "Default")
      (node (ref "ML1") (pin "1") (pinfunction "MH1_1") (pintype "passive+no_connect"))
    )
    (net (code "54") (name "unconnected-(ML1-MH2-Pad2)") (class "Default")
      (node (ref "ML1") (pin "2") (pinfunction "MH2_2") (pintype "passive+no_connect"))
    )
    (net (code "55") (name "unconnected-(U1-DOUT0-Pad45)") (class "Default")
      (node (ref "U1") (pin "45") (pinfunction "DOUT0_45") (pintype "output+no_connect"))
    )
    (net (code "56") (name "unconnected-(U1-DOUT1-Pad44)") (class "Default")
      (node (ref "U1") (pin "44") (pinfunction "DOUT1_44") (pintype "output+no_connect"))
    )
    (net (code "57") (name "unconnected-(U1-NC-Pad36)") (class "Default")
      (node (ref "U1") (pin "36") (pinfunction "NC_36") (pintype "tri_state+no_connect"))
    )
    (net (code "58") (name "unconnected-(U1-NC-Pad37)") (class "Default")
      (node (ref "U1") (pin "37") (pinfunction "NC_37") (pintype "tri_state+no_connect"))
    )
    (net (code "59") (name "unconnected-(U1-SER_DATAOUT_N-Pad4)") (class "Default")
      (node (ref "U1") (pin "4") (pinfunction "SER_DATAOUT_N_4") (pintype "output+no_connect"))
    )
    (net (code "60") (name "unconnected-(U1-SER_DATAOUT_P-Pad5)") (class "Default")
      (node (ref "U1") (pin "5") (pinfunction "SER_DATAOUT_P_5") (pintype "output+no_connect"))
    )
    (net (code "61") (name "unconnected-(U1-SHFT_CLKOUT_N-Pad2)") (class "Default")
      (node (ref "U1") (pin "2") (pinfunction "SHFT_CLKOUT_N_2") (pintype "output+no_connect"))
    )
    (net (code "62") (name "unconnected-(U1-SHFT_CLKOUT_P-Pad3)") (class "Default")
      (node (ref "U1") (pin "3") (pinfunction "SHFT_CLKOUT_P_3") (pintype "output+no_connect"))
    )
    (net (code "63") (name "unconnected-(U1-STFRM_OUT-Pad26)") (class "Default")
      (node (ref "U1") (pin "26") (pinfunction "STFRM_OUT_26") (pintype "bidirectional+no_connect"))
    )
    (net (code "64") (name "unconnected-(U1-STLN_OUT-Pad22)") (class "Default")
      (node (ref "U1") (pin "22") (pinfunction "STLN_OUT_22") (pintype "bidirectional+no_connect"))
    )
    (net (code "65") (name "unconnected-(U2-MIC_N-Pad17)") (class "Default")
      (node (ref "U2") (pin "17") (pinfunction "MIC_N_17") (pintype "input+no_connect"))
    )
    (net (code "66") (name "unconnected-(U2-MIC_P-Pad16)") (class "Default")
      (node (ref "U2") (pin "16") (pinfunction "MIC_P_16") (pintype "input+no_connect"))
    )
    (net (code "67") (name "unconnected-(U3-OSCIN{slash}PA1-Pad2)") (class "Default")
      (node (ref "U3") (pin "2") (pinfunction "OSCIN/PA1_2") (pintype "passive+no_connect"))
    )
    (net (code "68") (name "unconnected-(U3-OSCOUT{slash}PA2-Pad3)") (class "Default")
      (node (ref "U3") (pin "3") (pinfunction "OSCOUT/PA2_3") (pintype "passive+no_connect"))
    )
    (net (code "69") (name "unconnected-(U3-PD2(HS){slash}AIN3{slash}{TM2_CH3]-Pad16)") (class "Default")
      (node (ref "U3") (pin "16") (pinfunction "PD2(HS)/AIN3/{TM2_CH3]_16") (pintype "passive+no_connect"))
    )
    (net (code "70") (name "unconnected-(U3-PD3(HS){slash}AIN4{slash}TM2_CH2{slash}ADC_ETR-Pad17)") (class "Default")
      (node (ref "U3") (pin "17") (pinfunction "PD3(HS)/AIN4/TM2_CH2/ADC_ETR_17") (pintype "passive+no_connect"))
    )
    (net (code "71") (name "unconnected-(U3-PD4(HS){slash}BEEP{slash}TM2_CH1{slash}UART1_CK-Pad18)") (class "Default")
      (node (ref "U3") (pin "18") (pinfunction "PD4(HS)/BEEP/TM2_CH1/UART1_CK_18") (pintype "passive+no_connect"))
    )
    (net (code "72") (name "unconnected-(U3-PD5(HS){slash}AIN5{slash}UART1_TX-Pad19)") (class "Default")
      (node (ref "U3") (pin "19") (pinfunction "PD5(HS)/AIN5/UART1_TX_19") (pintype "passive+no_connect"))
    )
    (net (code "73") (name "unconnected-(U3-PD6(HS){slash}AIN6{slash}UART1_RX-Pad20)") (class "Default")
      (node (ref "U3") (pin "20") (pinfunction "PD6(HS)/AIN6/UART1_RX_20") (pintype "passive+no_connect"))
    )
    (net (code "74") (name "unconnected-(U4-NC-Pad2)") (class "Default")
      (node (ref "U4") (pin "2") (pinfunction "NC_2") (pintype "passive+no_connect"))
    )
    (net (code "75") (name "unconnected-(X1-Pad2)") (class "Default")
      (node (ref "X1") (pin "2") (pinfunction "2_2") (pintype "passive+no_connect"))
    )
    (net (code "76") (name "unconnected-(X1-Pad4)") (class "Default")
      (node (ref "X1") (pin "4") (pinfunction "4_4") (pintype "passive+no_connect"))
    )
  )
)
